# racing_robot.net
KiCad netlist of a schematic drawn in EAGLE
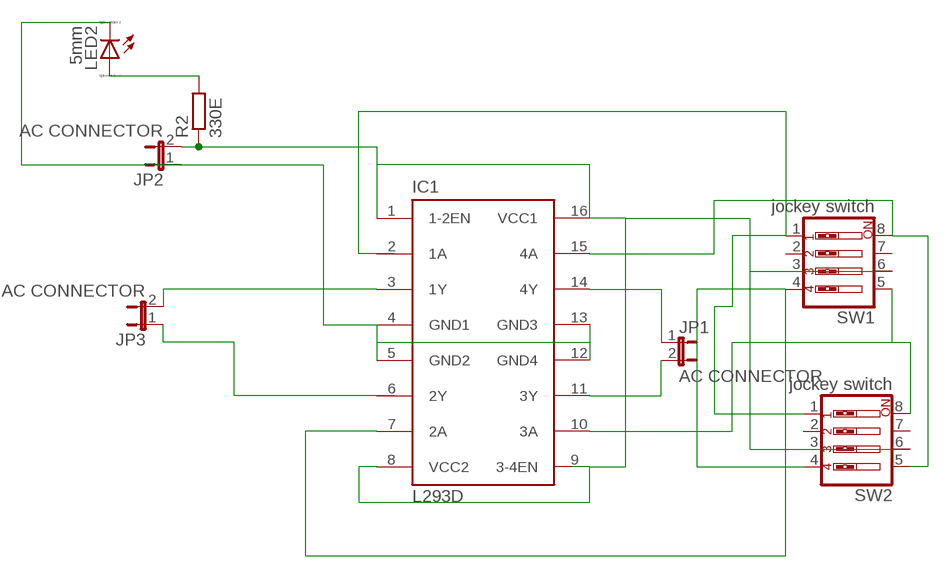
[diagram p0: schematic, sheet 1]

(export (version "E")
  (design (tool "Eeschema 10.0.6"))
  (components
    (comp (ref "IC1")
      (value "L293D")
      (footprint "eagle-import:DIL16")
      (libsource (lib "eagle-import") (part "L293D"))
    )
    (comp (ref "JP1")
      (value "AC CONNECTOR")
      (footprint "eagle-import:JP1")
      (libsource (lib "eagle-import") (part "JP1E"))
    )
    (comp (ref "JP2")
      (value "AC CONNECTOR")
      (footprint "eagle-import:JP1")
      (libsource (lib "eagle-import") (part "JP1E"))
    )
    (comp (ref "JP3")
      (value "AC CONNECTOR")
      (footprint "eagle-import:JP1")
      (libsource (lib "eagle-import") (part "JP1E"))
    )
    (comp (ref "LED2")
      (value "5mm")
      (footprint "eagle-import:LED_LD260")
      (libsource (lib "eagle-import") (part "LED_ELD260"))
    )
    (comp (ref "R2")
      (value "330E")
      (footprint "eagle-import:0204_7")
      (libsource (lib "eagle-import") (part "R-EU_0204/7"))
    )
    (comp (ref "SW1")
      (value "jockey switch")
      (footprint "eagle-import:EDG-04")
      (libsource (lib "eagle-import") (part "SW_DIP-4"))
    )
    (comp (ref "SW2")
      (value "jockey switch")
      (footprint "eagle-import:EDG-04")
      (libsource (lib "eagle-import") (part "SW_DIP-4"))
    )
  )
  (nets
    (net (code "1") (name "Net-(IC1-1-2EN)") (class "Default")
      (node (ref "IC1") (pin "1") (pinfunction "1-2EN_1") (pintype "input"))
      (node (ref "IC1") (pin "16") (pinfunction "VCC1_16") (pintype "power_in"))
      (node (ref "IC1") (pin "8") (pinfunction "VCC2_8") (pintype "power_in"))
      (node (ref "IC1") (pin "9") (pinfunction "3-4EN_9") (pintype "input"))
      (node (ref "JP2") (pin "2") (pinfunction "2_2") (pintype "passive"))
      (node (ref "R2") (pin "1") (pinfunction "1_1") (pintype "passive"))
      (node (ref "SW1") (pin "3") (pinfunction "3_3") (pintype "passive"))
      (node (ref "SW1") (pin "6") (pinfunction "6_6") (pintype "passive"))
      (node (ref "SW2") (pin "3") (pinfunction "3_3") (pintype "passive"))
      (node (ref "SW2") (pin "6") (pinfunction "6_6") (pintype "passive"))
    )
    (net (code "2") (name "Net-(IC1-1A)") (class "Default")
      (node (ref "IC1") (pin "2") (pinfunction "1A_2") (pintype "input"))
      (node (ref "SW1") (pin "1") (pinfunction "1_1") (pintype "passive"))
      (node (ref "SW2") (pin "1") (pinfunction "1_1") (pintype "passive"))
    )
    (net (code "3") (name "Net-(IC1-1Y)") (class "Default")
      (node (ref "IC1") (pin "3") (pinfunction "1Y_3") (pintype "output"))
      (node (ref "JP3") (pin "2") (pinfunction "2_2") (pintype "passive"))
    )
    (net (code "4") (name "Net-(IC1-2A)") (class "Default")
      (node (ref "IC1") (pin "7") (pinfunction "2A_7") (pintype "input"))
      (node (ref "SW1") (pin "4") (pinfunction "4_4") (pintype "passive"))
      (node (ref "SW2") (pin "4") (pinfunction "4_4") (pintype "passive"))
    )
    (net (code "5") (name "Net-(IC1-2Y)") (class "Default")
      (node (ref "IC1") (pin "6") (pinfunction "2Y_6") (pintype "output"))
      (node (ref "JP3") (pin "1") (pinfunction "1_1") (pintype "passive"))
    )
    (net (code "6") (name "Net-(IC1-3A)") (class "Default")
      (node (ref "IC1") (pin "10") (pinfunction "3A_10") (pintype "input"))
      (node (ref "SW1") (pin "5") (pinfunction "5_5") (pintype "passive"))
      (node (ref "SW2") (pin "8") (pinfunction "8_8") (pintype "passive"))
    )
    (net (code "7") (name "Net-(IC1-3Y)") (class "Default")
      (node (ref "IC1") (pin "11") (pinfunction "3Y_11") (pintype "output"))
      (node (ref "JP1") (pin "2") (pinfunction "2_2") (pintype "passive"))
    )
    (net (code "8") (name "Net-(IC1-4A)") (class "Default")
      (node (ref "IC1") (pin "15") (pinfunction "4A_15") (pintype "input"))
      (node (ref "SW1") (pin "8") (pinfunction "8_8") (pintype "passive"))
      (node (ref "SW2") (pin "5") (pinfunction "5_5") (pintype "passive"))
    )
    (net (code "9") (name "Net-(IC1-4Y)") (class "Default")
      (node (ref "IC1") (pin "14") (pinfunction "4Y_14") (pintype "output"))
      (node (ref "JP1") (pin "1") (pinfunction "1_1") (pintype "passive"))
    )
    (net (code "10") (name "Net-(IC1-GND1)") (class "Default")
      (node (ref "IC1") (pin "12") (pinfunction "GND4_12") (pintype "power_in"))
      (node (ref "IC1") (pin "13") (pinfunction "GND3_13") (pintype "power_in"))
      (node (ref "IC1") (pin "4") (pinfunction "GND1_4") (pintype "power_in"))
      (node (ref "IC1") (pin "5") (pinfunction "GND2_5") (pintype "power_in"))
      (node (ref "JP2") (pin "1") (pinfunction "1_1") (pintype "passive"))
      (node (ref "LED2") (pin "K") (pinfunction "C_K") (pintype "passive"))
    )
    (net (code "11") (name "Net-(LED2-PadA)") (class "Default")
      (node (ref "LED2") (pin "A") (pinfunction "A_A") (pintype "passive"))
      (node (ref "R2") (pin "2") (pinfunction "2_2") (pintype "passive"))
    )
    (net (code "12") (name "unconnected-(SW1-Pad2)") (class "Default")
      (node (ref "SW1") (pin "2") (pinfunction "2_2") (pintype "passive"))
    )
    (net (code "13") (name "unconnected-(SW1-Pad7)") (class "Default")
      (node (ref "SW1") (pin "7") (pinfunction "7_7") (pintype "passive"))
    )
    (net (code "14") (name "unconnected-(SW2-Pad2)") (class "Default")
      (node (ref "SW2") (pin "2") (pinfunction "2_2") (pintype "passive"))
    )
    (net (code "15") (name "unconnected-(SW2-Pad7)") (class "Default")
      (node (ref "SW2") (pin "7") (pinfunction "7_7") (pintype "passive"))
    )
  )
)
